# FUC.net
KiCad netlist of a schematic drawn in Altium Designer
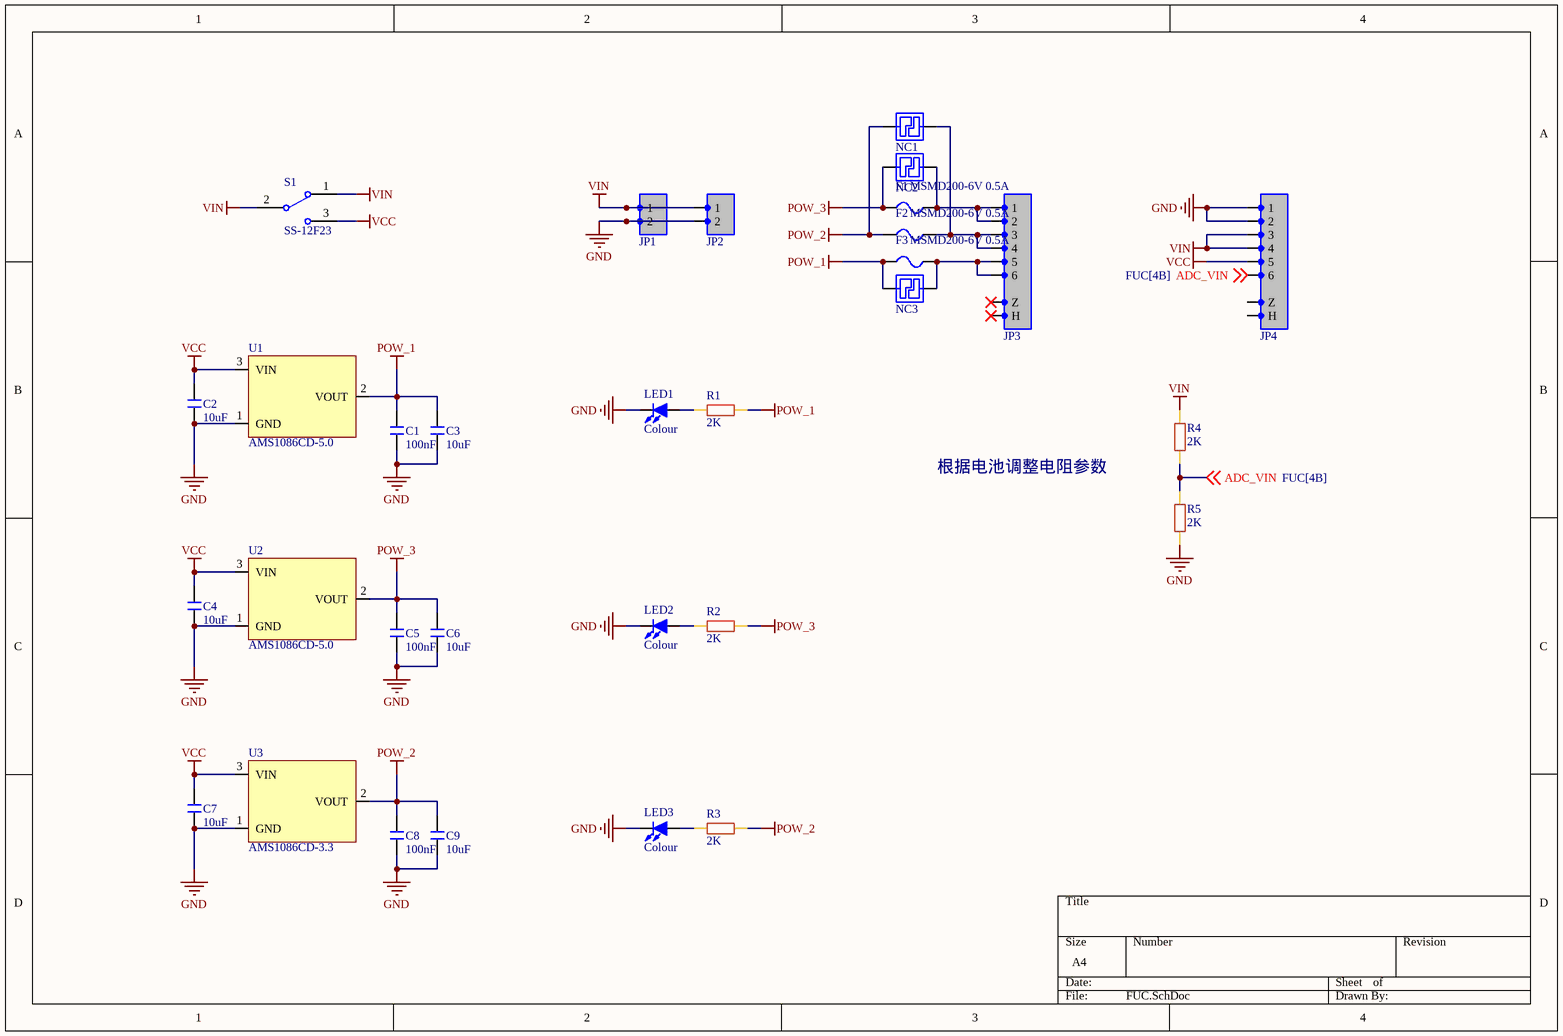
[diagram p0: FUC.SchDoc]

(export (version "E")
  (design (tool "Eeschema 10.0.6"))
  (components
    (comp (ref "C1")
      (value "100nF")
      (footprint "C 0603_L")
      (description "无极性贴片电容")
      (fields (field (name "版权归属") "源创客"))
      (libsource (lib "3.2-电容") (part "C"))
    )
    (comp (ref "C2")
      (value "10uF")
      (footprint "C 0603_L")
      (description "无极性贴片电容")
      (fields (field (name "版权归属") "源创客"))
      (libsource (lib "3.2-电容") (part "C"))
    )
    (comp (ref "C3")
      (value "10uF")
      (footprint "C 0603_L")
      (description "无极性贴片电容")
      (fields (field (name "版权归属") "源创客"))
      (libsource (lib "3.2-电容") (part "C"))
    )
    (comp (ref "C4")
      (value "10uF")
      (footprint "C 0603_L")
      (description "无极性贴片电容")
      (fields (field (name "版权归属") "源创客"))
      (libsource (lib "3.2-电容") (part "C"))
    )
    (comp (ref "C5")
      (value "100nF")
      (footprint "C 0603_L")
      (description "无极性贴片电容")
      (fields (field (name "版权归属") "源创客"))
      (libsource (lib "3.2-电容") (part "C"))
    )
    (comp (ref "C6")
      (value "10uF")
      (footprint "C 0603_L")
      (description "无极性贴片电容")
      (fields (field (name "版权归属") "源创客"))
      (libsource (lib "3.2-电容") (part "C"))
    )
    (comp (ref "C7")
      (value "10uF")
      (footprint "C 0603_L")
      (description "无极性贴片电容")
      (fields (field (name "版权归属") "源创客"))
      (libsource (lib "3.2-电容") (part "C"))
    )
    (comp (ref "C8")
      (value "100nF")
      (footprint "C 0603_L")
      (description "无极性贴片电容")
      (fields (field (name "版权归属") "源创客"))
      (libsource (lib "3.2-电容") (part "C"))
    )
    (comp (ref "C9")
      (value "10uF")
      (footprint "C 0603_L")
      (description "无极性贴片电容")
      (fields (field (name "版权归属") "源创客"))
      (libsource (lib "3.2-电容") (part "C"))
    )
    (comp (ref "F1")
      (value "MSMD200-6V 0.5A")
      (footprint "FU 0805")
      (description "贴片保险丝")
      (fields (field (name "版权归属") "源创客"))
      (libsource (lib "6.3-保险丝") (part "FU"))
    )
    (comp (ref "F2")
      (value "MSMD200-6V 0.5A")
      (footprint "FU 0805")
      (description "贴片保险丝")
      (fields (field (name "版权归属") "源创客"))
      (libsource (lib "6.3-保险丝") (part "FU"))
    )
    (comp (ref "F3")
      (value "MSMD200-6V 0.5A")
      (footprint "FU 0805")
      (description "贴片保险丝")
      (fields (field (name "版权归属") "源创客"))
      (libsource (lib "6.3-保险丝") (part "FU"))
    )
    (comp (ref "JP1")
      (value "HDR-1X2")
      (footprint "XH2.54-WI-2P")
      (description "2P接插件")
      (fields (field (name "版权归属") "源创客"))
      (libsource (lib "14.6-接插件-脚距2.54") (part "Header 2"))
    )
    (comp (ref "JP2")
      (value "HDR-1X2")
      (footprint "HDR2.54-LI-2P")
      (description "2P接插件")
      (fields (field (name "版权归属") "源创客"))
      (libsource (lib "14.6-接插件-脚距2.54") (part "Header 2"))
    )
    (comp (ref "JP3")
      (value "HDR-1X6")
      (footprint "HDR2.54-LI-6P")
      (description "6P接插件")
      (fields (field (name "版权归属") "源创客"))
      (libsource (lib "14.6-接插件-脚距2.54") (part "Header 6"))
    )
    (comp (ref "JP4")
      (value "HDR-1X6")
      (footprint "HDR2.54-LI-6P")
      (description "6P接插件")
      (fields (field (name "版权归属") "源创客"))
      (libsource (lib "14.6-接插件-脚距2.54") (part "Header 6"))
    )
    (comp (ref "LED1")
      (value "Colour")
      (footprint "LED 0603R")
      (description "贴片LED")
      (fields (field (name "版权归属") "源创客"))
      (libsource (lib "7.1-LED") (part "LED-SMD"))
    )
    (comp (ref "LED2")
      (value "Colour")
      (footprint "LED 0603R")
      (description "贴片LED")
      (fields (field (name "版权归属") "源创客"))
      (libsource (lib "7.1-LED") (part "LED-SMD"))
    )
    (comp (ref "LED3")
      (value "Colour")
      (footprint "LED 0603R")
      (description "贴片LED")
      (fields (field (name "版权归属") "源创客"))
      (libsource (lib "7.1-LED") (part "LED-SMD"))
    )
    (comp (ref "NC1")
      (value "Node")
      (footprint "NODE-2")
      (description "大电流节点")
      (libsource (lib "13.1-未分类器件") (part "NODE"))
    )
    (comp (ref "NC2")
      (value "Node")
      (footprint "NODE-2")
      (description "大电流节点")
      (libsource (lib "13.1-未分类器件") (part "NODE"))
    )
    (comp (ref "NC3")
      (value "Node")
      (footprint "NODE-2")
      (description "大电流节点")
      (libsource (lib "13.1-未分类器件") (part "NODE"))
    )
    (comp (ref "R1")
      (value "2K")
      (footprint "R 0603_L")
      (description "贴片电阻1%精度")
      (libsource (lib "Propitious Clouds_SCHLIB") (part "电阻"))
    )
    (comp (ref "R2")
      (value "2K")
      (footprint "R 0603_L")
      (description "贴片电阻1%精度")
      (libsource (lib "Propitious Clouds_SCHLIB") (part "电阻"))
    )
    (comp (ref "R3")
      (value "2K")
      (footprint "R 0603_L")
      (description "贴片电阻1%精度")
      (libsource (lib "Propitious Clouds_SCHLIB") (part "电阻"))
    )
    (comp (ref "R4")
      (value "2K")
      (footprint "R 0603_L")
      (description "贴片电阻1%精度")
      (libsource (lib "Propitious Clouds_SCHLIB") (part "电阻"))
    )
    (comp (ref "R5")
      (value "2K")
      (footprint "R 0603_L")
      (description "贴片电阻1%精度")
      (libsource (lib "Propitious Clouds_SCHLIB") (part "电阻"))
    )
    (comp (ref "S1")
      (value "SS-12F23")
      (footprint "SS-12D10")
      (description "1路拨动开关")
      (fields (field (name "版权归属") "源创客"))
      (libsource (lib "6.2-开关") (part "SSW-1P"))
    )
    (comp (ref "U1")
      (value "AMS1086CD-5.0")
      (footprint "TO252")
      (libsource (lib "Schlib1") (part "AMS1086CD-5.0"))
    )
    (comp (ref "U2")
      (value "AMS1086CD-5.0")
      (footprint "TO252")
      (libsource (lib "Schlib1") (part "AMS1086CD-5.0"))
    )
    (comp (ref "U3")
      (value "AMS1086CD-3.3")
      (footprint "TO252")
      (libsource (lib "Schlib1") (part "AMS1086CD-5.0"))
    )
  )
  (nets
    (net (code "1") (name "ADC_VIN") (class "Default")
      (node (ref "JP4") (pin "6") (pinfunction "6_6") (pintype "passive"))
      (node (ref "R4") (pin "2") (pinfunction "2_2") (pintype "passive"))
      (node (ref "R5") (pin "1") (pinfunction "1_1") (pintype "passive"))
    )
    (net (code "2") (name "GND") (class "Default")
      (node (ref "C1") (pin "2") (pinfunction "2_2") (pintype "passive"))
      (node (ref "C2") (pin "2") (pinfunction "2_2") (pintype "passive"))
      (node (ref "C3") (pin "2") (pinfunction "2_2") (pintype "passive"))
      (node (ref "C4") (pin "2") (pinfunction "2_2") (pintype "passive"))
      (node (ref "C5") (pin "2") (pinfunction "2_2") (pintype "passive"))
      (node (ref "C6") (pin "2") (pinfunction "2_2") (pintype "passive"))
      (node (ref "C7") (pin "2") (pinfunction "2_2") (pintype "passive"))
      (node (ref "C8") (pin "2") (pinfunction "2_2") (pintype "passive"))
      (node (ref "C9") (pin "2") (pinfunction "2_2") (pintype "passive"))
      (node (ref "JP1") (pin "2") (pinfunction "2_2") (pintype "passive"))
      (node (ref "JP2") (pin "2") (pinfunction "2_2") (pintype "passive"))
      (node (ref "JP4") (pin "1") (pinfunction "1_1") (pintype "passive"))
      (node (ref "JP4") (pin "2") (pinfunction "2_2") (pintype "passive"))
      (node (ref "LED1") (pin "2") (pinfunction "K_2") (pintype "passive"))
      (node (ref "LED2") (pin "2") (pinfunction "K_2") (pintype "passive"))
      (node (ref "LED3") (pin "2") (pinfunction "K_2") (pintype "passive"))
      (node (ref "R5") (pin "2") (pinfunction "2_2") (pintype "passive"))
      (node (ref "U1") (pin "1") (pinfunction "GND_1") (pintype "passive"))
      (node (ref "U2") (pin "1") (pinfunction "GND_1") (pintype "passive"))
      (node (ref "U3") (pin "1") (pinfunction "GND_1") (pintype "passive"))
    )
    (net (code "3") (name "Net-(F1-Pad2)") (class "Default")
      (node (ref "F1") (pin "2") (pinfunction "2_2") (pintype "passive"))
      (node (ref "JP3") (pin "1") (pinfunction "1_1") (pintype "passive"))
      (node (ref "JP3") (pin "2") (pinfunction "2_2") (pintype "passive"))
      (node (ref "NC2") (pin "2") (pinfunction "2_2") (pintype "passive"))
    )
    (net (code "4") (name "Net-(F2-Pad2)") (class "Default")
      (node (ref "F2") (pin "2") (pinfunction "2_2") (pintype "passive"))
      (node (ref "JP3") (pin "3") (pinfunction "3_3") (pintype "passive"))
      (node (ref "JP3") (pin "4") (pinfunction "4_4") (pintype "passive"))
      (node (ref "NC1") (pin "2") (pinfunction "2_2") (pintype "passive"))
    )
    (net (code "5") (name "Net-(F3-Pad2)") (class "Default")
      (node (ref "F3") (pin "2") (pinfunction "2_2") (pintype "passive"))
      (node (ref "JP3") (pin "5") (pinfunction "5_5") (pintype "passive"))
      (node (ref "JP3") (pin "6") (pinfunction "6_6") (pintype "passive"))
      (node (ref "NC3") (pin "2") (pinfunction "2_2") (pintype "passive"))
    )
    (net (code "6") (name "Net-(LED1-A)") (class "Default")
      (node (ref "LED1") (pin "1") (pinfunction "A_1") (pintype "passive"))
      (node (ref "R1") (pin "2") (pinfunction "2_2") (pintype "passive"))
    )
    (net (code "7") (name "Net-(LED2-A)") (class "Default")
      (node (ref "LED2") (pin "1") (pinfunction "A_1") (pintype "passive"))
      (node (ref "R2") (pin "2") (pinfunction "2_2") (pintype "passive"))
    )
    (net (code "8") (name "Net-(LED3-A)") (class "Default")
      (node (ref "LED3") (pin "1") (pinfunction "A_1") (pintype "passive"))
      (node (ref "R3") (pin "2") (pinfunction "2_2") (pintype "passive"))
    )
    (net (code "9") (name "POW_1") (class "Default")
      (node (ref "C1") (pin "1") (pinfunction "1_1") (pintype "passive"))
      (node (ref "C3") (pin "1") (pinfunction "1_1") (pintype "passive"))
      (node (ref "F3") (pin "1") (pinfunction "1_1") (pintype "passive"))
      (node (ref "NC3") (pin "1") (pinfunction "1_1") (pintype "passive"))
      (node (ref "R1") (pin "1") (pinfunction "1_1") (pintype "passive"))
      (node (ref "U1") (pin "2") (pinfunction "VOUT_2") (pintype "passive"))
    )
    (net (code "10") (name "POW_2") (class "Default")
      (node (ref "C8") (pin "1") (pinfunction "1_1") (pintype "passive"))
      (node (ref "C9") (pin "1") (pinfunction "1_1") (pintype "passive"))
      (node (ref "F2") (pin "1") (pinfunction "1_1") (pintype "passive"))
      (node (ref "NC1") (pin "1") (pinfunction "1_1") (pintype "passive"))
      (node (ref "R3") (pin "1") (pinfunction "1_1") (pintype "passive"))
      (node (ref "U3") (pin "2") (pinfunction "VOUT_2") (pintype "passive"))
    )
    (net (code "11") (name "POW_3") (class "Default")
      (node (ref "C5") (pin "1") (pinfunction "1_1") (pintype "passive"))
      (node (ref "C6") (pin "1") (pinfunction "1_1") (pintype "passive"))
      (node (ref "F1") (pin "1") (pinfunction "1_1") (pintype "passive"))
      (node (ref "NC2") (pin "1") (pinfunction "1_1") (pintype "passive"))
      (node (ref "R2") (pin "1") (pinfunction "1_1") (pintype "passive"))
      (node (ref "U2") (pin "2") (pinfunction "VOUT_2") (pintype "passive"))
    )
    (net (code "12") (name "VCC") (class "Default")
      (node (ref "C2") (pin "1") (pinfunction "1_1") (pintype "passive"))
      (node (ref "C4") (pin "1") (pinfunction "1_1") (pintype "passive"))
      (node (ref "C7") (pin "1") (pinfunction "1_1") (pintype "passive"))
      (node (ref "JP4") (pin "5") (pinfunction "5_5") (pintype "passive"))
      (node (ref "S1") (pin "3") (pinfunction "3_3") (pintype "passive"))
      (node (ref "U1") (pin "3") (pinfunction "VIN_3") (pintype "passive"))
      (node (ref "U2") (pin "3") (pinfunction "VIN_3") (pintype "passive"))
      (node (ref "U3") (pin "3") (pinfunction "VIN_3") (pintype "passive"))
    )
    (net (code "13") (name "VIN") (class "Default")
      (node (ref "JP1") (pin "1") (pinfunction "1_1") (pintype "passive"))
      (node (ref "JP2") (pin "1") (pinfunction "1_1") (pintype "passive"))
      (node (ref "JP4") (pin "3") (pinfunction "3_3") (pintype "passive"))
      (node (ref "JP4") (pin "4") (pinfunction "4_4") (pintype "passive"))
      (node (ref "R4") (pin "1") (pinfunction "1_1") (pintype "passive"))
      (node (ref "S1") (pin "1") (pinfunction "1_1") (pintype "passive"))
      (node (ref "S1") (pin "2") (pinfunction "2_2") (pintype "passive"))
    )
    (net (code "14") (name "unconnected-(JP3-H-Pad100)") (class "Default")
      (node (ref "JP3") (pin "100") (pinfunction "H_100") (pintype "passive+no_connect"))
    )
    (net (code "15") (name "unconnected-(JP3-Z-Pad0)") (class "Default")
      (node (ref "JP3") (pin "0") (pinfunction "Z_0") (pintype "passive+no_connect"))
    )
    (net (code "16") (name "unconnected-(JP4-H-Pad100)") (class "Default")
      (node (ref "JP4") (pin "100") (pinfunction "H_100") (pintype "passive"))
    )
    (net (code "17") (name "unconnected-(JP4-Z-Pad0)") (class "Default")
      (node (ref "JP4") (pin "0") (pinfunction "Z_0") (pintype "passive"))
    )
  )
)
